# Sheet1.net
KiCad netlist of a schematic drawn in Altium Designer
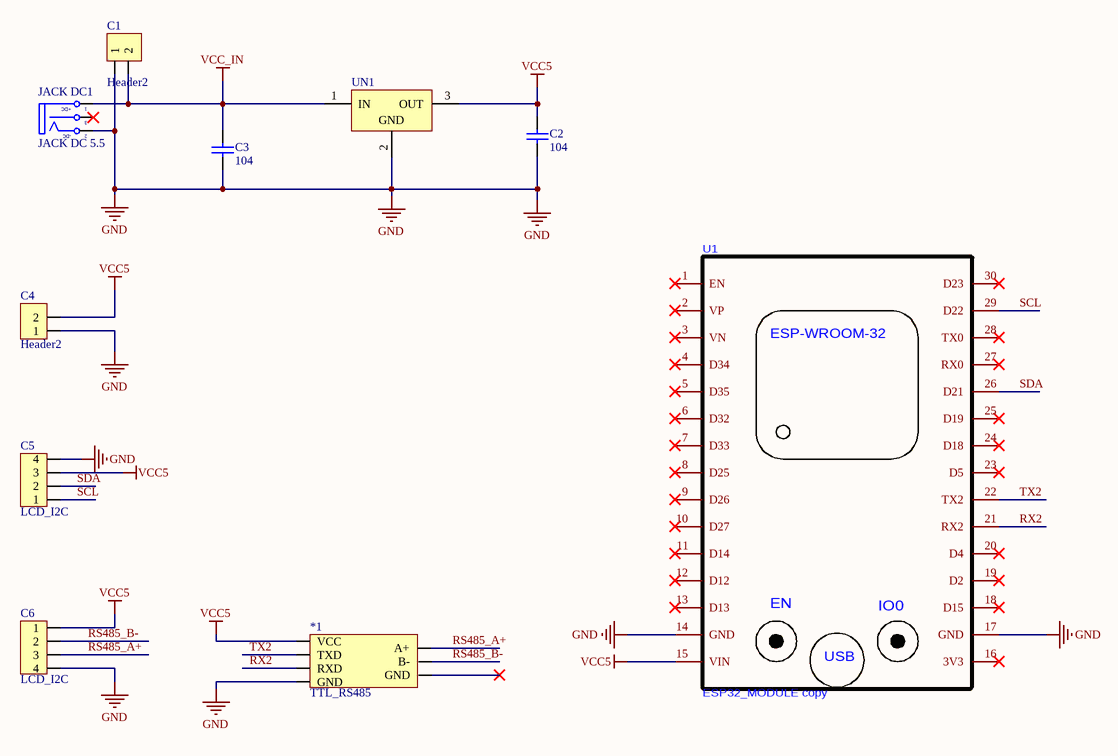
[diagram p0: Sheet1.SchDoc]

(export (version "E")
  (design (tool "Eeschema 10.0.6"))
  (components
    (comp (ref "*1")
      (value "TTL_RS485")
      (footprint "RS-485 Module")
      (libsource (lib "myLib_v1") (part "TTL_RS485"))
    )
    (comp (ref "C1")
      (value "Header2")
      (footprint "Header2")
      (description "Header IDC, 2 x 1 Pin Vertical 2.54mm Pitch (Non-Boxed, Male)")
      (fields
        (field (name "MANUFACTURER") "Würth Elektronik eiSos GmbH")
        (field (name "PARTNO") "613002143121")
        (field (name "CREATED BY") "Karrer Zheng")
      )
      (libsource (lib "myLib_v1") (part "Header2"))
    )
    (comp (ref "C2")
      (value "104")
      (footprint "tu gom")
      (description "Cắm")
      (libsource (lib "Altium_Lib_by_KhueNguyenCreator") (part "Tu gom 104 50V"))
    )
    (comp (ref "C3")
      (value "104")
      (footprint "tu gom")
      (description "Cắm")
      (libsource (lib "Altium_Lib_by_KhueNguyenCreator") (part "Tu gom 104 50V"))
    )
    (comp (ref "C4")
      (value "Header2")
      (footprint "Header2")
      (description "Header IDC, 2 x 1 Pin Vertical 2.54mm Pitch (Non-Boxed, Male)")
      (fields
        (field (name "MANUFACTURER") "Würth Elektronik eiSos GmbH")
        (field (name "PARTNO") "613002143121")
        (field (name "CREATED BY") "Karrer Zheng")
      )
      (libsource (lib "") (part "Header2_1"))
    )
    (comp (ref "C5")
      (value "LCD_I2C")
      (footprint "Header4")
      (description "Header IDC, 4 x 1 Pin Vertical 2.54mm Pitch (Non-Boxed, Male)")
      (fields
        (field (name "MANUFACTURER") "Würth Elektronik eiSos GmbH")
        (field (name "PARTNO") "613002143121")
        (field (name "CREATED BY") "Karrer Zheng")
      )
      (libsource (lib "") (part "Header4_1"))
    )
    (comp (ref "C6")
      (value "LCD_I2C")
      (footprint "Header4")
      (description "Header IDC, 4 x 1 Pin Vertical 2.54mm Pitch (Non-Boxed, Male)")
      (fields
        (field (name "MANUFACTURER") "Würth Elektronik eiSos GmbH")
        (field (name "PARTNO") "613002143121")
        (field (name "CREATED BY") "Karrer Zheng")
      )
      (libsource (lib "myLib_v1") (part "Header4"))
    )
    (comp (ref "JACK DC1")
      (value "JACK DC 5.5")
      (footprint "JACK DC 5.5")
      (libsource (lib "Altium_Lib_by_KhueNguyenCreator") (part "JACK DC 5.5"))
    )
    (comp (ref "U1")
      (value "ESP32_MODULE copy")
      (footprint "ESP32-WIFIMODULE-FOOTPRINT")
      (libsource (lib "myLib_v1") (part "ESP32_MODULE copy"))
    )
    (comp (ref "UN1")
      (value "L78M05CP")
      (footprint "QTO-220H2")
      (description "Positive Voltage Regulator")
      (fields (field (name "PUBLISHER") "Altium Limited"))
      (libsource (lib "syhaunguyen") (part "L78M05CP"))
    )
  )
  (nets
    (net (code "1") (name "/RS485_A+") (class "Default")
      (node (ref "*1") (pin "7") (pinfunction "A+_7") (pintype "passive"))
      (node (ref "C6") (pin "3") (pinfunction "3_3") (pintype "passive"))
    )
    (net (code "2") (name "/RS485_B-") (class "Default")
      (node (ref "*1") (pin "6") (pinfunction "B-_6") (pintype "passive"))
      (node (ref "C6") (pin "2") (pinfunction "2_2") (pintype "passive"))
    )
    (net (code "3") (name "/RX2") (class "Default")
      (node (ref "*1") (pin "3") (pinfunction "RXD_3") (pintype "passive"))
      (node (ref "U1") (pin "21") (pinfunction "RX2_21") (pintype "passive"))
    )
    (net (code "4") (name "/SCL") (class "Default")
      (node (ref "C5") (pin "1") (pinfunction "1_1") (pintype "passive"))
      (node (ref "U1") (pin "29") (pinfunction "D22_29") (pintype "passive"))
    )
    (net (code "5") (name "/SDA") (class "Default")
      (node (ref "C5") (pin "2") (pinfunction "2_2") (pintype "passive"))
      (node (ref "U1") (pin "26") (pinfunction "D21_26") (pintype "passive"))
    )
    (net (code "6") (name "/TX2") (class "Default")
      (node (ref "*1") (pin "2") (pinfunction "TXD_2") (pintype "passive"))
      (node (ref "U1") (pin "22") (pinfunction "TX2_22") (pintype "passive"))
    )
    (net (code "7") (name "GND") (class "Default")
      (node (ref "*1") (pin "4") (pinfunction "GND_4") (pintype "passive"))
      (node (ref "C1") (pin "1") (pinfunction "1_1") (pintype "passive"))
      (node (ref "C2") (pin "2") (pinfunction "2_2") (pintype "passive"))
      (node (ref "C3") (pin "2") (pinfunction "2_2") (pintype "passive"))
      (node (ref "C4") (pin "1") (pinfunction "1_1") (pintype "passive"))
      (node (ref "C5") (pin "4") (pinfunction "4_4") (pintype "passive"))
      (node (ref "C6") (pin "4") (pinfunction "4_4") (pintype "passive"))
      (node (ref "JACK DC1") (pin "2") (pinfunction "TN_2") (pintype "passive"))
      (node (ref "U1") (pin "14") (pinfunction "GND_14") (pintype "passive"))
      (node (ref "U1") (pin "17") (pinfunction "GND_17") (pintype "passive"))
      (node (ref "UN1") (pin "2") (pinfunction "GND_2") (pintype "power_in"))
    )
    (net (code "8") (name "VCC5") (class "Default")
      (node (ref "*1") (pin "1") (pinfunction "VCC_1") (pintype "passive"))
      (node (ref "C2") (pin "1") (pinfunction "1_1") (pintype "passive"))
      (node (ref "C4") (pin "2") (pinfunction "2_2") (pintype "passive"))
      (node (ref "C5") (pin "3") (pinfunction "3_3") (pintype "passive"))
      (node (ref "C6") (pin "1") (pinfunction "1_1") (pintype "passive"))
      (node (ref "U1") (pin "15") (pinfunction "VIN_15") (pintype "passive"))
      (node (ref "UN1") (pin "3") (pinfunction "OUT_3") (pintype "power_in"))
    )
    (net (code "9") (name "VCC_IN") (class "Default")
      (node (ref "C1") (pin "2") (pinfunction "2_2") (pintype "passive"))
      (node (ref "C3") (pin "1") (pinfunction "1_1") (pintype "passive"))
      (node (ref "JACK DC1") (pin "1") (pinfunction "T_1") (pintype "passive"))
      (node (ref "UN1") (pin "1") (pinfunction "IN_1") (pintype "power_in"))
    )
    (net (code "10") (name "unconnected-(*1-GND-Pad5)") (class "Default")
      (node (ref "*1") (pin "5") (pinfunction "GND_5") (pintype "passive+no_connect"))
    )
    (net (code "11") (name "unconnected-(JACK DC1-S-Pad3)") (class "Default")
      (node (ref "JACK DC1") (pin "3") (pinfunction "S_3") (pintype "power_in+no_connect"))
    )
    (net (code "12") (name "unconnected-(U1-3V3-Pad16)") (class "Default")
      (node (ref "U1") (pin "16") (pinfunction "3V3_16") (pintype "passive+no_connect"))
    )
    (net (code "13") (name "unconnected-(U1-D2-Pad19)") (class "Default")
      (node (ref "U1") (pin "19") (pinfunction "D2_19") (pintype "passive+no_connect"))
    )
    (net (code "14") (name "unconnected-(U1-D4-Pad20)") (class "Default")
      (node (ref "U1") (pin "20") (pinfunction "D4_20") (pintype "passive+no_connect"))
    )
    (net (code "15") (name "unconnected-(U1-D5-Pad23)") (class "Default")
      (node (ref "U1") (pin "23") (pinfunction "D5_23") (pintype "passive+no_connect"))
    )
    (net (code "16") (name "unconnected-(U1-D12-Pad12)") (class "Default")
      (node (ref "U1") (pin "12") (pinfunction "D12_12") (pintype "passive+no_connect"))
    )
    (net (code "17") (name "unconnected-(U1-D13-Pad13)") (class "Default")
      (node (ref "U1") (pin "13") (pinfunction "D13_13") (pintype "passive+no_connect"))
    )
    (net (code "18") (name "unconnected-(U1-D14-Pad11)") (class "Default")
      (node (ref "U1") (pin "11") (pinfunction "D14_11") (pintype "passive+no_connect"))
    )
    (net (code "19") (name "unconnected-(U1-D15-Pad18)") (class "Default")
      (node (ref "U1") (pin "18") (pinfunction "D15_18") (pintype "passive+no_connect"))
    )
    (net (code "20") (name "unconnected-(U1-D18-Pad24)") (class "Default")
      (node (ref "U1") (pin "24") (pinfunction "D18_24") (pintype "passive+no_connect"))
    )
    (net (code "21") (name "unconnected-(U1-D19-Pad25)") (class "Default")
      (node (ref "U1") (pin "25") (pinfunction "D19_25") (pintype "passive+no_connect"))
    )
    (net (code "22") (name "unconnected-(U1-D23-Pad30)") (class "Default")
      (node (ref "U1") (pin "30") (pinfunction "D23_30") (pintype "passive+no_connect"))
    )
    (net (code "23") (name "unconnected-(U1-D25-Pad8)") (class "Default")
      (node (ref "U1") (pin "8") (pinfunction "D25_8") (pintype "passive+no_connect"))
    )
    (net (code "24") (name "unconnected-(U1-D26-Pad9)") (class "Default")
      (node (ref "U1") (pin "9") (pinfunction "D26_9") (pintype "passive+no_connect"))
    )
    (net (code "25") (name "unconnected-(U1-D27-Pad10)") (class "Default")
      (node (ref "U1") (pin "10") (pinfunction "D27_10") (pintype "passive+no_connect"))
    )
    (net (code "26") (name "unconnected-(U1-D32-Pad6)") (class "Default")
      (node (ref "U1") (pin "6") (pinfunction "D32_6") (pintype "passive+no_connect"))
    )
    (net (code "27") (name "unconnected-(U1-D33-Pad7)") (class "Default")
      (node (ref "U1") (pin "7") (pinfunction "D33_7") (pintype "passive+no_connect"))
    )
    (net (code "28") (name "unconnected-(U1-D34-Pad4)") (class "Default")
      (node (ref "U1") (pin "4") (pinfunction "D34_4") (pintype "passive+no_connect"))
    )
    (net (code "29") (name "unconnected-(U1-D35-Pad5)") (class "Default")
      (node (ref "U1") (pin "5") (pinfunction "D35_5") (pintype "passive+no_connect"))
    )
    (net (code "30") (name "unconnected-(U1-EN-Pad1)") (class "Default")
      (node (ref "U1") (pin "1") (pinfunction "EN_1") (pintype "passive+no_connect"))
    )
    (net (code "31") (name "unconnected-(U1-RX0-Pad27)") (class "Default")
      (node (ref "U1") (pin "27") (pinfunction "RX0_27") (pintype "passive+no_connect"))
    )
    (net (code "32") (name "unconnected-(U1-TX0-Pad28)") (class "Default")
      (node (ref "U1") (pin "28") (pinfunction "TX0_28") (pintype "passive+no_connect"))
    )
    (net (code "33") (name "unconnected-(U1-VN-Pad3)") (class "Default")
      (node (ref "U1") (pin "3") (pinfunction "VN_3") (pintype "passive+no_connect"))
    )
    (net (code "34") (name "unconnected-(U1-VP-Pad2)") (class "Default")
      (node (ref "U1") (pin "2") (pinfunction "VP_2") (pintype "passive+no_connect"))
    )
  )
)
